# MCU.net
KiCad netlist of a schematic drawn in Altium Designer
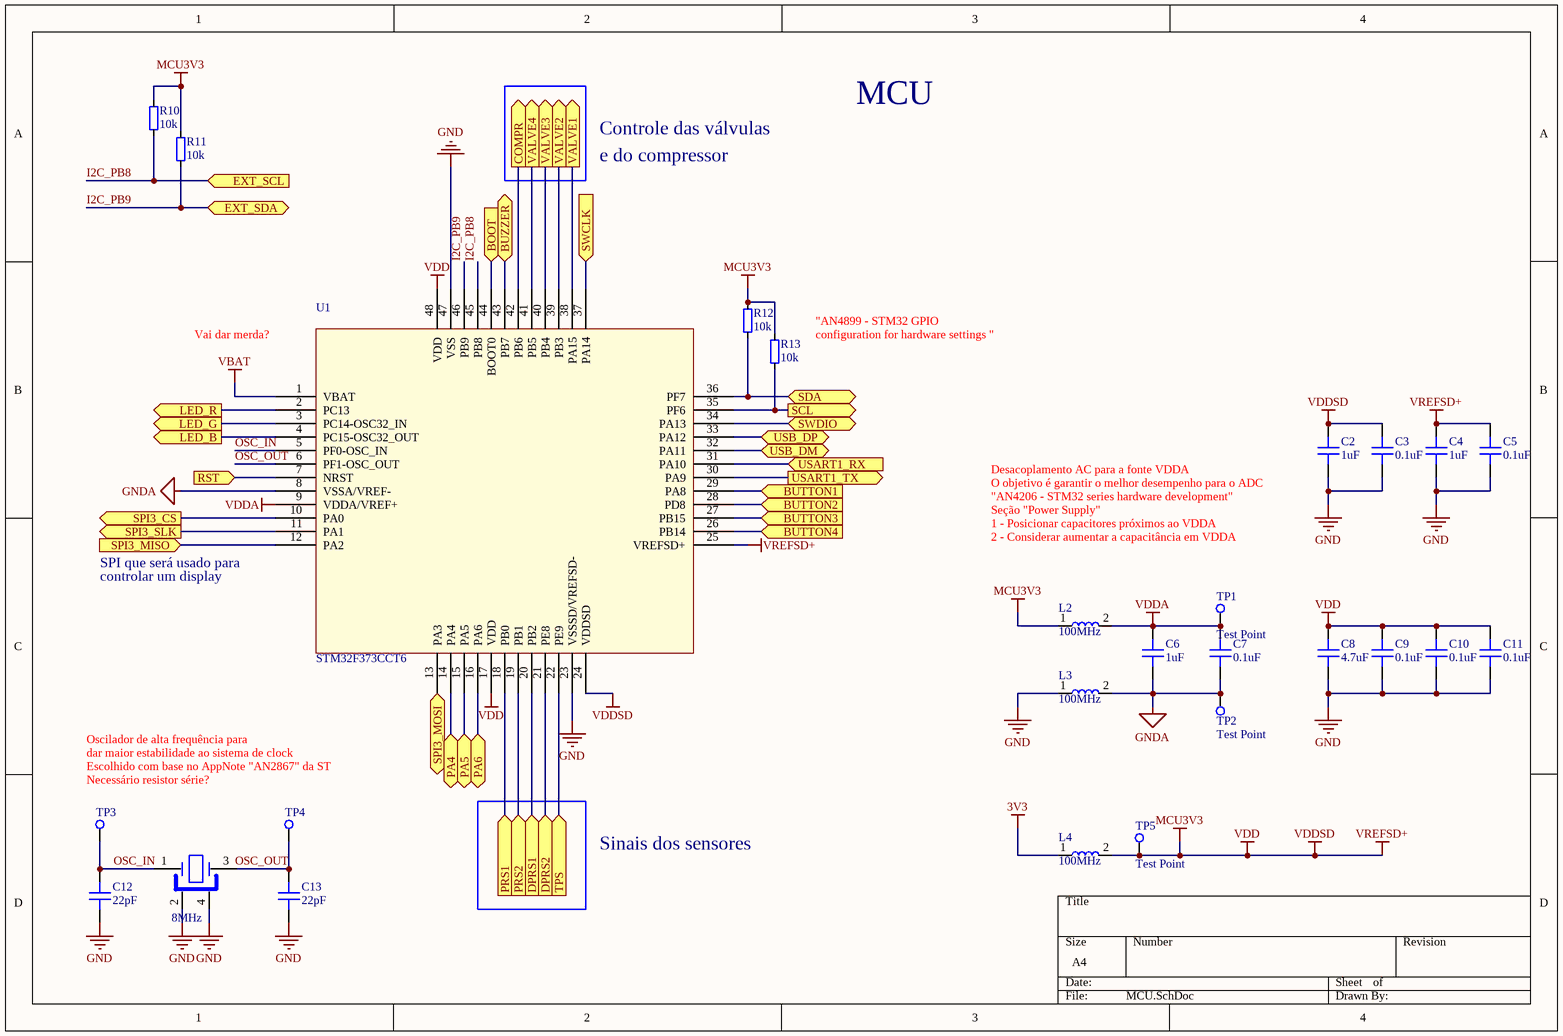
[diagram p0: MCU.SchDoc]

(export (version "E")
  (design (tool "Eeschema 10.0.6"))
  (components
    (comp (ref "C2")
      (value "1uF")
      (footprint "C_0805")
      (description "SMD/SMT 0805 50V 1uF 10% AEC-Q200 Ceramic")
      (fields (field (name "VOLTAGE") "50V") (field (name "MANUFACTURER") "Taiyo Yuden"))
      (libsource (lib "RespiradorLib") (part "C_0805_UMF212B7105KGHT"))
    )
    (comp (ref "C3")
      (value "0.1uF")
      (footprint "C_0805")
      (description "SMD/SMT 50V 0.1uF X7R 0805 10% Ceramic")
      (fields (field (name "VOLTAGE") "50V") (field (name "MANUFACTURER") "KEMET"))
      (libsource (lib "RespiradorLib") (part "C_0805_C0805C104K5RAC7411"))
    )
    (comp (ref "C4")
      (value "1uF")
      (footprint "C_0805")
      (description "SMD/SMT 0805 50V 1uF 10% AEC-Q200 Ceramic")
      (fields (field (name "VOLTAGE") "50V") (field (name "MANUFACTURER") "Taiyo Yuden"))
      (libsource (lib "RespiradorLib") (part "C_0805_UMF212B7105KGHT"))
    )
    (comp (ref "C5")
      (value "0.1uF")
      (footprint "C_0805")
      (description "SMD/SMT 50V 0.1uF X7R 0805 10% Ceramic")
      (fields (field (name "VOLTAGE") "50V") (field (name "MANUFACTURER") "KEMET"))
      (libsource (lib "RespiradorLib") (part "C_0805_C0805C104K5RAC7411"))
    )
    (comp (ref "C6")
      (value "1uF")
      (footprint "C_0805")
      (description "SMD/SMT 0805 50V 1uF 10% AEC-Q200 Ceramic")
      (fields (field (name "VOLTAGE") "50V") (field (name "MANUFACTURER") "Taiyo Yuden"))
      (libsource (lib "RespiradorLib") (part "C_0805_UMF212B7105KGHT"))
    )
    (comp (ref "C7")
      (value "0.1uF")
      (footprint "C_0805")
      (description "SMD/SMT 50V 0.1uF X7R 0805 10% Ceramic")
      (fields (field (name "VOLTAGE") "50V") (field (name "MANUFACTURER") "KEMET"))
      (libsource (lib "RespiradorLib") (part "C_0805_C0805C104K5RAC7411"))
    )
    (comp (ref "C8")
      (value "4.7uF")
      (footprint "C_0805")
      (description "SMD/SMT 0805 50VDC 4.7uF 10% X7R CERAMIC")
      (fields (field (name "VOLTAGE") "50V") (field (name "MANUFACTURER") "TDK"))
      (libsource (lib "RespiradorLib") (part "C_0805_C2012X7R1H475K125AC"))
    )
    (comp (ref "C9")
      (value "0.1uF")
      (footprint "C_0805")
      (description "SMD/SMT 50V 0.1uF X7R 0805 10% Ceramic")
      (fields (field (name "VOLTAGE") "50V") (field (name "MANUFACTURER") "KEMET"))
      (libsource (lib "RespiradorLib") (part "C_0805_C0805C104K5RAC7411"))
    )
    (comp (ref "C10")
      (value "0.1uF")
      (footprint "C_0805")
      (description "SMD/SMT 50V 0.1uF X7R 0805 10% Ceramic")
      (fields (field (name "VOLTAGE") "50V") (field (name "MANUFACTURER") "KEMET"))
      (libsource (lib "RespiradorLib") (part "C_0805_C0805C104K5RAC7411"))
    )
    (comp (ref "C11")
      (value "0.1uF")
      (footprint "C_0805")
      (description "SMD/SMT 50V 0.1uF X7R 0805 10% Ceramic")
      (fields (field (name "VOLTAGE") "50V") (field (name "MANUFACTURER") "KEMET"))
      (libsource (lib "RespiradorLib") (part "C_0805_C0805C104K5RAC7411"))
    )
    (comp (ref "C12")
      (value "22pF")
      (footprint "C_0603")
      (description "SMD/SMT 50V 22pF 0603 C0G 5%")
      (fields (field (name "VOLTAGE") "50V") (field (name "MANUFACTURER") "KEMET"))
      (libsource (lib "RespiradorLib") (part "C_0603_C0603C220J5GACTU"))
    )
    (comp (ref "C13")
      (value "22pF")
      (footprint "C_0603")
      (description "SMD/SMT 50V 22pF 0603 C0G 5%")
      (fields (field (name "VOLTAGE") "50V") (field (name "MANUFACTURER") "KEMET"))
      (libsource (lib "RespiradorLib") (part "C_0603_C0603C220J5GACTU"))
    )
    (comp (ref "L2")
      (value "100MHz")
      (footprint "L_0603")
      (description "FERRITE BEAD 270 OHM 0603")
      (libsource (lib "RespiradorLib") (part "L_0603_BKP1608HS271-T"))
    )
    (comp (ref "L3")
      (value "100MHz")
      (footprint "L_0603")
      (description "FERRITE BEAD 270 OHM 0603")
      (libsource (lib "RespiradorLib") (part "L_0603_BKP1608HS271-T"))
    )
    (comp (ref "L4")
      (value "100MHz")
      (footprint "L_0603")
      (description "FERRITE BEAD 270 OHM 0603")
      (libsource (lib "RespiradorLib") (part "L_0603_BKP1608HS271-T"))
    )
    (comp (ref "R10")
      (value "10k")
      (footprint "R_0805")
      (description "RES 10K OHM 1/8W 5% 0805 SMD")
      (fields (field (name "MANUFACTURER") "Panasonic - ECG") (field (name "VOLTAGE") "150V"))
      (libsource (lib "RespiradorLib") (part "R_0805_ERJ-6GEYJ103V"))
    )
    (comp (ref "R11")
      (value "10k")
      (footprint "R_0805")
      (description "RES 10K OHM 1/8W 5% 0805 SMD")
      (fields (field (name "MANUFACTURER") "Panasonic - ECG") (field (name "VOLTAGE") "150V"))
      (libsource (lib "RespiradorLib") (part "R_0805_ERJ-6GEYJ103V"))
    )
    (comp (ref "R12")
      (value "10k")
      (footprint "R_0805")
      (description "RES 10K OHM 1/8W 5% 0805 SMD")
      (fields (field (name "MANUFACTURER") "Panasonic - ECG") (field (name "VOLTAGE") "150V"))
      (libsource (lib "RespiradorLib") (part "R_0805_ERJ-6GEYJ103V"))
    )
    (comp (ref "R13")
      (value "10k")
      (footprint "R_0805")
      (description "RES 10K OHM 1/8W 5% 0805 SMD")
      (fields (field (name "MANUFACTURER") "Panasonic - ECG") (field (name "VOLTAGE") "150V"))
      (libsource (lib "RespiradorLib") (part "R_0805_ERJ-6GEYJ103V"))
    )
    (comp (ref "TP1")
      (value "Test Point")
      (footprint "Test_Point")
      (libsource (lib "RespiradorLib") (part "Test Point"))
    )
    (comp (ref "TP2")
      (value "Test Point")
      (footprint "Test_Point")
      (libsource (lib "RespiradorLib") (part "Test Point"))
    )
    (comp (ref "TP3")
      (value "Test Point")
      (footprint "Test_Point")
      (libsource (lib "RespiradorLib") (part "Test Point"))
    )
    (comp (ref "TP4")
      (value "Test Point")
      (footprint "Test_Point")
      (libsource (lib "RespiradorLib") (part "Test Point"))
    )
    (comp (ref "TP5")
      (value "Test Point")
      (footprint "Test_Point")
      (libsource (lib "RespiradorLib") (part "Test Point"))
    )
    (comp (ref "U1")
      (value "STM32F373CCT6")
      (footprint "MCU_STM32F373CC7")
      (description "CORTEX-M4 ST MCU")
      (libsource (lib "RespiradorLib") (part "MCU_STM32F373CCT6"))
    )
    (comp (ref "XTAL1")
      (value "8MHz")
      (footprint "XTAL_8MHZ")
      (description "ABRACON Crystals 8MHz")
      (fields (field (name "PART NUMBER") "ABMM2-8.000MHZ-E2-T"))
      (libsource (lib "RespiradorLib") (part "XTAL_8MHz"))
    )
  )
  (nets
    (net (code "1") (name "/BOOT") (class "Default")
      (node (ref "U1") (pin "44") (pinfunction "BOOT0_44") (pintype "passive"))
    )
    (net (code "2") (name "/BUTTON1") (class "Default")
      (node (ref "U1") (pin "29") (pinfunction "PA8_29") (pintype "passive"))
    )
    (net (code "3") (name "/BUTTON2") (class "Default")
      (node (ref "U1") (pin "28") (pinfunction "PD8_28") (pintype "passive"))
    )
    (net (code "4") (name "/BUTTON3") (class "Default")
      (node (ref "U1") (pin "27") (pinfunction "PB15_27") (pintype "passive"))
    )
    (net (code "5") (name "/BUTTON4") (class "Default")
      (node (ref "U1") (pin "26") (pinfunction "PB14_26") (pintype "passive"))
    )
    (net (code "6") (name "/BUZZER") (class "Default")
      (node (ref "U1") (pin "43") (pinfunction "PB7_43") (pintype "passive"))
    )
    (net (code "7") (name "/COMPR") (class "Default")
      (node (ref "U1") (pin "42") (pinfunction "PB6_42") (pintype "passive"))
    )
    (net (code "8") (name "/DPRS1") (class "Default")
      (node (ref "U1") (pin "20") (pinfunction "PB2_20") (pintype "passive"))
    )
    (net (code "9") (name "/DPRS2") (class "Default")
      (node (ref "U1") (pin "21") (pinfunction "PE8_21") (pintype "passive"))
    )
    (net (code "10") (name "/I2C_PB8") (class "Default")
      (node (ref "R10") (pin "1") (pinfunction "1_1") (pintype "passive"))
      (node (ref "U1") (pin "45") (pinfunction "PB8_45") (pintype "passive"))
    )
    (net (code "11") (name "/I2C_PB9") (class "Default")
      (node (ref "R11") (pin "1") (pinfunction "1_1") (pintype "passive"))
      (node (ref "U1") (pin "46") (pinfunction "PB9_46") (pintype "passive"))
    )
    (net (code "12") (name "/LED_B") (class "Default")
      (node (ref "U1") (pin "4") (pinfunction "PC15-OSC32_OUT_4") (pintype "passive"))
    )
    (net (code "13") (name "/LED_G") (class "Default")
      (node (ref "U1") (pin "3") (pinfunction "PC14-OSC32_IN_3") (pintype "passive"))
    )
    (net (code "14") (name "/LED_R") (class "Default")
      (node (ref "U1") (pin "2") (pinfunction "PC13_2") (pintype "passive"))
    )
    (net (code "15") (name "/OSC_IN") (class "Default")
      (node (ref "C12") (pin "2") (pinfunction "2_2") (pintype "passive"))
      (node (ref "TP3") (pin "1") (pinfunction "TP_1") (pintype "passive"))
      (node (ref "U1") (pin "5") (pinfunction "PF0-OSC_IN_5") (pintype "passive"))
      (node (ref "XTAL1") (pin "1") (pinfunction "1_1") (pintype "passive"))
    )
    (net (code "16") (name "/OSC_OUT") (class "Default")
      (node (ref "U1") (pin "6") (pinfunction "PF1-OSC_OUT_6") (pintype "passive"))
    )
    (net (code "17") (name "/PA4") (class "Default")
      (node (ref "U1") (pin "14") (pinfunction "PA4_14") (pintype "passive"))
    )
    (net (code "18") (name "/PA5") (class "Default")
      (node (ref "U1") (pin "15") (pinfunction "PA5_15") (pintype "passive"))
    )
    (net (code "19") (name "/PA6") (class "Default")
      (node (ref "U1") (pin "16") (pinfunction "PA6_16") (pintype "passive"))
    )
    (net (code "20") (name "/PRS1") (class "Default")
      (node (ref "U1") (pin "18") (pinfunction "PB0_18") (pintype "passive"))
    )
    (net (code "21") (name "/PRS2") (class "Default")
      (node (ref "U1") (pin "19") (pinfunction "PB1_19") (pintype "passive"))
    )
    (net (code "22") (name "/RST") (class "Default")
      (node (ref "U1") (pin "7") (pinfunction "NRST_7") (pintype "passive"))
    )
    (net (code "23") (name "/SCL") (class "Default")
      (node (ref "R13") (pin "1") (pinfunction "1_1") (pintype "passive"))
      (node (ref "U1") (pin "35") (pinfunction "PF6_35") (pintype "passive"))
    )
    (net (code "24") (name "/SDA") (class "Default")
      (node (ref "R12") (pin "1") (pinfunction "1_1") (pintype "passive"))
      (node (ref "U1") (pin "36") (pinfunction "PF7_36") (pintype "passive"))
    )
    (net (code "25") (name "/SPI3_CS") (class "Default")
      (node (ref "U1") (pin "10") (pinfunction "PA0_10") (pintype "passive"))
    )
    (net (code "26") (name "/SPI3_MISO") (class "Default")
      (node (ref "U1") (pin "12") (pinfunction "PA2_12") (pintype "passive"))
    )
    (net (code "27") (name "/SPI3_MOSI") (class "Default")
      (node (ref "U1") (pin "13") (pinfunction "PA3_13") (pintype "passive"))
    )
    (net (code "28") (name "/SPI3_SLK") (class "Default")
      (node (ref "U1") (pin "11") (pinfunction "PA1_11") (pintype "passive"))
    )
    (net (code "29") (name "/SWCLK") (class "Default")
      (node (ref "U1") (pin "37") (pinfunction "PA14_37") (pintype "passive"))
    )
    (net (code "30") (name "/SWDIO") (class "Default")
      (node (ref "U1") (pin "34") (pinfunction "PA13_34") (pintype "passive"))
    )
    (net (code "31") (name "/TPS") (class "Default")
      (node (ref "U1") (pin "22") (pinfunction "PE9_22") (pintype "passive"))
    )
    (net (code "32") (name "/USART1_RX") (class "Default")
      (node (ref "U1") (pin "31") (pinfunction "PA10_31") (pintype "passive"))
    )
    (net (code "33") (name "/USART1_TX") (class "Default")
      (node (ref "U1") (pin "30") (pinfunction "PA9_30") (pintype "passive"))
    )
    (net (code "34") (name "/USB_DM") (class "Default")
      (node (ref "U1") (pin "32") (pinfunction "PA11_32") (pintype "passive"))
    )
    (net (code "35") (name "/USB_DP") (class "Default")
      (node (ref "U1") (pin "33") (pinfunction "PA12_33") (pintype "passive"))
    )
    (net (code "36") (name "/VALVE1") (class "Default")
      (node (ref "U1") (pin "38") (pinfunction "PA15_38") (pintype "passive"))
    )
    (net (code "37") (name "/VALVE2") (class "Default")
      (node (ref "U1") (pin "39") (pinfunction "PB3_39") (pintype "passive"))
    )
    (net (code "38") (name "/VALVE3") (class "Default")
      (node (ref "U1") (pin "40") (pinfunction "PB4_40") (pintype "passive"))
    )
    (net (code "39") (name "/VALVE4") (class "Default")
      (node (ref "U1") (pin "41") (pinfunction "PB5_41") (pintype "passive"))
    )
    (net (code "40") (name "3V3") (class "Default")
      (node (ref "L4") (pin "1") (pinfunction "1_1") (pintype "passive"))
    )
    (net (code "41") (name "GND") (class "Default")
      (node (ref "C10") (pin "2") (pinfunction "2_2") (pintype "passive"))
      (node (ref "C11") (pin "2") (pinfunction "2_2") (pintype "passive"))
      (node (ref "C12") (pin "1") (pinfunction "1_1") (pintype "passive"))
      (node (ref "C13") (pin "1") (pinfunction "1_1") (pintype "passive"))
      (node (ref "C2") (pin "1") (pinfunction "1_1") (pintype "passive"))
      (node (ref "C3") (pin "2") (pinfunction "2_2") (pintype "passive"))
      (node (ref "C4") (pin "1") (pinfunction "1_1") (pintype "passive"))
      (node (ref "C5") (pin "2") (pinfunction "2_2") (pintype "passive"))
      (node (ref "C8") (pin "2") (pinfunction "2_2") (pintype "passive"))
      (node (ref "C9") (pin "2") (pinfunction "2_2") (pintype "passive"))
      (node (ref "L3") (pin "1") (pinfunction "1_1") (pintype "passive"))
      (node (ref "U1") (pin "23") (pinfunction "VSSSD/VREFSD-_23") (pintype "passive"))
      (node (ref "U1") (pin "47") (pinfunction "VSS_47") (pintype "passive"))
      (node (ref "XTAL1") (pin "2") (pinfunction "2_2") (pintype "passive"))
      (node (ref "XTAL1") (pin "4") (pinfunction "4_4") (pintype "passive"))
    )
    (net (code "42") (name "GNDA") (class "Default")
      (node (ref "C6") (pin "1") (pinfunction "1_1") (pintype "passive"))
      (node (ref "C7") (pin "1") (pinfunction "1_1") (pintype "passive"))
      (node (ref "L3") (pin "2") (pinfunction "2_2") (pintype "passive"))
      (node (ref "TP2") (pin "1") (pinfunction "TP_1") (pintype "passive"))
      (node (ref "U1") (pin "8") (pinfunction "VSSA/VREF-_8") (pintype "passive"))
    )
    (net (code "43") (name "MCU3V3") (class "Default")
      (node (ref "C10") (pin "1") (pinfunction "1_1") (pintype "passive"))
      (node (ref "C11") (pin "1") (pinfunction "1_1") (pintype "passive"))
      (node (ref "C2") (pin "2") (pinfunction "2_2") (pintype "passive"))
      (node (ref "C3") (pin "1") (pinfunction "1_1") (pintype "passive"))
      (node (ref "C4") (pin "2") (pinfunction "2_2") (pintype "passive"))
      (node (ref "C5") (pin "1") (pinfunction "1_1") (pintype "passive"))
      (node (ref "C8") (pin "1") (pinfunction "1_1") (pintype "passive"))
      (node (ref "C9") (pin "1") (pinfunction "1_1") (pintype "passive"))
      (node (ref "L2") (pin "1") (pinfunction "1_1") (pintype "passive"))
      (node (ref "L4") (pin "2") (pinfunction "2_2") (pintype "passive"))
      (node (ref "R10") (pin "2") (pinfunction "2_2") (pintype "passive"))
      (node (ref "R11") (pin "2") (pinfunction "2_2") (pintype "passive"))
      (node (ref "R12") (pin "2") (pinfunction "2_2") (pintype "passive"))
      (node (ref "R13") (pin "2") (pinfunction "2_2") (pintype "passive"))
      (node (ref "TP5") (pin "1") (pinfunction "TP_1") (pintype "passive"))
      (node (ref "U1") (pin "17") (pinfunction "VDD_17") (pintype "passive"))
      (node (ref "U1") (pin "24") (pinfunction "VDDSD_24") (pintype "passive"))
      (node (ref "U1") (pin "25") (pinfunction "VREFSD+_25") (pintype "passive"))
      (node (ref "U1") (pin "48") (pinfunction "VDD_48") (pintype "passive"))
    )
    (net (code "44") (name "Net-(TP4-TP)") (class "Default")
      (node (ref "C13") (pin "2") (pinfunction "2_2") (pintype "passive"))
      (node (ref "TP4") (pin "1") (pinfunction "TP_1") (pintype "passive"))
      (node (ref "XTAL1") (pin "3") (pinfunction "3_3") (pintype "passive"))
    )
    (net (code "45") (name "VBAT") (class "Default")
      (node (ref "U1") (pin "1") (pinfunction "VBAT_1") (pintype "passive"))
    )
    (net (code "46") (name "VDDA") (class "Default")
      (node (ref "C6") (pin "2") (pinfunction "2_2") (pintype "passive"))
      (node (ref "C7") (pin "2") (pinfunction "2_2") (pintype "passive"))
      (node (ref "L2") (pin "2") (pinfunction "2_2") (pintype "passive"))
      (node (ref "TP1") (pin "1") (pinfunction "TP_1") (pintype "passive"))
      (node (ref "U1") (pin "9") (pinfunction "VDDA/VREF+_9") (pintype "passive"))
    )
  )
)
